# LB-w3-DOUBLE_OR-v03_rev4.net
KiCad netlist of a schematic drawn in EAGLE
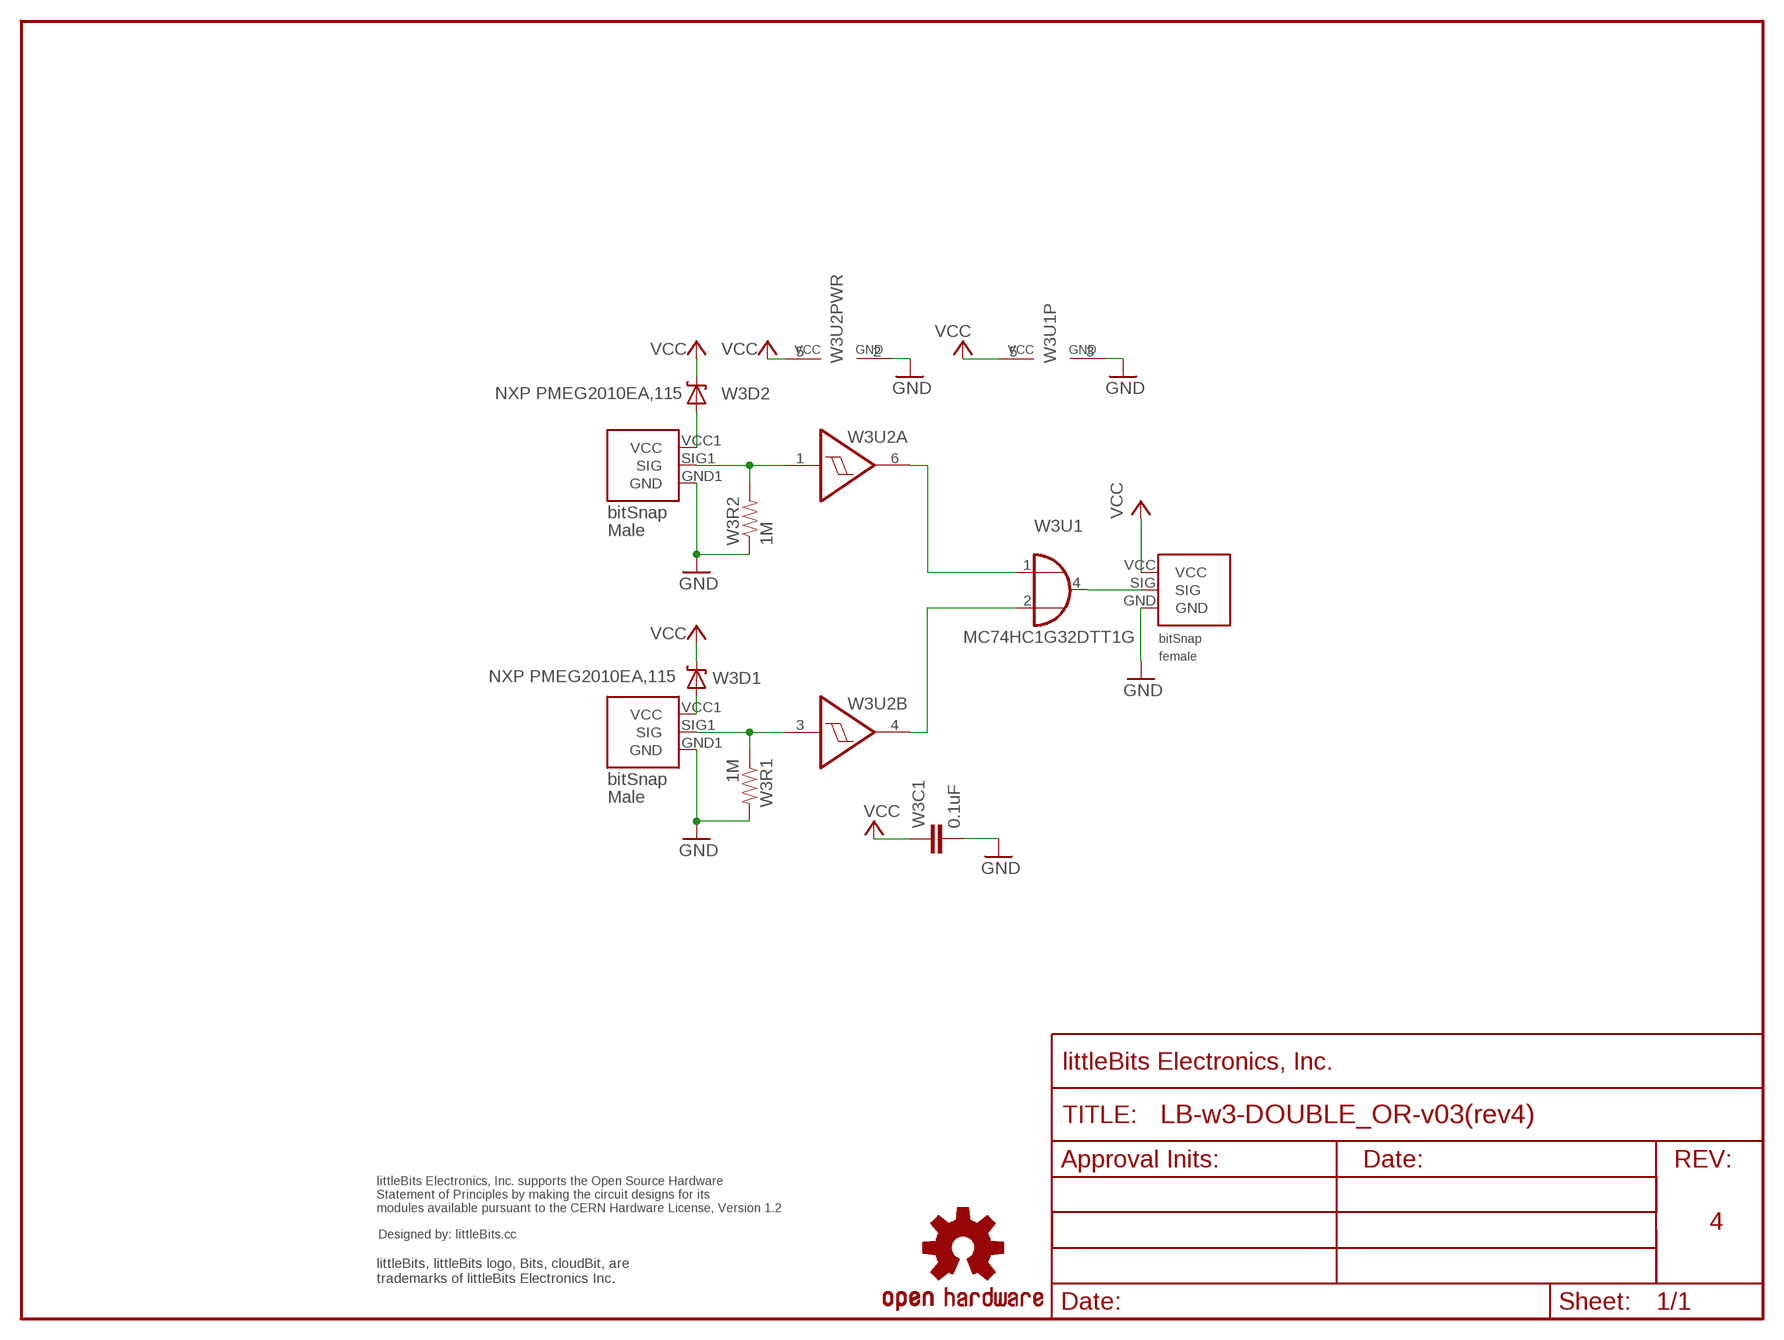
[diagram p0: schematic, sheet 1]

(export (version "E")
  (design (tool "Eeschema 10.0.6"))
  (components
    (comp (ref "U$1")
      (value "OSHWCREDIT")
      (footprint "eagle-import:OSHWCREDIT")
      (libsource (lib "eagle-import") (part "OSHWCREDIT"))
    )
    (comp (ref "U$2")
      (value "OSHW-LOGOL")
      (footprint "eagle-import:OSHW-LOGO-L")
      (libsource (lib "eagle-import") (part "OSHW-LOGOL"))
    )
    (comp (ref "U$16")
      (value "FRAME-LETTER-OHWOHW")
      (footprint "eagle-import:FABDWG01-OHW")
      (libsource (lib "eagle-import") (part "FRAME-LETTER-OHWOHW"))
    )
    (comp (ref "W3BSF1")
      (value "BITSNAP_V03_FEMALE")
      (footprint "eagle-import:BITSNAP_V03_FEMALE")
      (libsource (lib "eagle-import") (part "BITSNAP_V03_FEMALE"))
    )
    (comp (ref "W3BSM1")
      (value "BITSNAP_V03_MALE")
      (footprint "eagle-import:BITSNAP_V03_MALE")
      (libsource (lib "eagle-import") (part "BITSNAP_V03_MALE"))
    )
    (comp (ref "W3BSM2")
      (value "BITSNAP_V03_MALE")
      (footprint "eagle-import:BITSNAP_V03_MALE")
      (libsource (lib "eagle-import") (part "BITSNAP_V03_MALE"))
    )
    (comp (ref "W3C1")
      (value "0.1uF")
      (footprint "eagle-import:CAP-0603")
      (libsource (lib "eagle-import") (part "CAPCAP-0603"))
    )
    (comp (ref "W3D1")
      (value "NXP PMEG2010EA,115")
      (footprint "eagle-import:SOD-323")
      (libsource (lib "eagle-import") (part "DIODE-ZENER-BZT52"))
    )
    (comp (ref "W3D2")
      (value "NXP PMEG2010EA,115")
      (footprint "eagle-import:SOD-323")
      (libsource (lib "eagle-import") (part "DIODE-ZENER-BZT52"))
    )
    (comp (ref "W3R1")
      (value "1M")
      (footprint "eagle-import:0603-RES")
      (libsource (lib "eagle-import") (part "RESISTOR0603-RES"))
    )
    (comp (ref "W3R2")
      (value "1M")
      (footprint "eagle-import:0603-RES")
      (libsource (lib "eagle-import") (part "RESISTOR0603-RES"))
    )
    (comp (ref "W3U1")
      (value "74AUC1G32DBV")
      (footprint "eagle-import:SOT23-5")
      (libsource (lib "eagle-import") (part "741G32DBVAUC"))
    )
    (comp (ref "W3U2")
      (value "SCHMITT_TRIGGER_NON_INVERTING NC7WZ17")
      (footprint "eagle-import:SC70-6")
      (libsource (lib "eagle-import") (part "SCHMITT_TRIGGER_NON_INVERTINGNC7WZ17"))
    )
  )
  (nets
    (net (code "1") (name "GND") (class "Default")
      (node (ref "W3BSF1") (pin "GND") (pinfunction "GND_GND") (pintype "bidirectional"))
      (node (ref "W3BSM1") (pin "GND1") (pinfunction "GND_GND1") (pintype "bidirectional"))
      (node (ref "W3BSM2") (pin "GND1") (pinfunction "GND_GND1") (pintype "bidirectional"))
      (node (ref "W3C1") (pin "2") (pinfunction "2_2") (pintype "passive"))
      (node (ref "W3R1") (pin "2") (pinfunction "2_2") (pintype "passive"))
      (node (ref "W3R2") (pin "1") (pinfunction "1_1") (pintype "passive"))
      (node (ref "W3U1") (pin "3") (pinfunction "GND_3") (pintype "power_in"))
      (node (ref "W3U2") (pin "2") (pinfunction "GND_2") (pintype "power_in"))
    )
    (net (code "2") (name "Net-(W3BSM1-SIG)") (class "Default")
      (node (ref "W3BSM1") (pin "SIG1") (pinfunction "SIG_SIG1") (pintype "bidirectional"))
      (node (ref "W3R2") (pin "2") (pinfunction "2_2") (pintype "passive"))
      (node (ref "W3U2") (pin "1") (pinfunction "I_1") (pintype "input"))
    )
    (net (code "3") (name "Net-(W3BSM1-VCC)") (class "Default")
      (node (ref "W3BSM1") (pin "VCC1") (pinfunction "VCC_VCC1") (pintype "bidirectional"))
      (node (ref "W3D2") (pin "2") (pinfunction "A_2") (pintype "passive"))
    )
    (net (code "4") (name "Net-(W3BSM2-SIG)") (class "Default")
      (node (ref "W3BSM2") (pin "SIG1") (pinfunction "SIG_SIG1") (pintype "bidirectional"))
      (node (ref "W3R1") (pin "1") (pinfunction "1_1") (pintype "passive"))
      (node (ref "W3U2") (pin "3") (pinfunction "I_3") (pintype "input"))
    )
    (net (code "5") (name "Net-(W3BSM2-VCC)") (class "Default")
      (node (ref "W3BSM2") (pin "VCC1") (pinfunction "VCC_VCC1") (pintype "bidirectional"))
      (node (ref "W3D1") (pin "2") (pinfunction "A_2") (pintype "passive"))
    )
    (net (code "6") (name "Net-(W3U1A-I0)") (class "Default")
      (node (ref "W3U1") (pin "1") (pinfunction "I0_1") (pintype "input"))
      (node (ref "W3U2") (pin "6") (pinfunction "O_6") (pintype "output"))
    )
    (net (code "7") (name "Net-(W3U1A-I1)") (class "Default")
      (node (ref "W3U1") (pin "2") (pinfunction "I1_2") (pintype "input"))
      (node (ref "W3U2") (pin "4") (pinfunction "O_4") (pintype "output"))
    )
    (net (code "8") (name "Net-(W3U1A-O)") (class "Default")
      (node (ref "W3BSF1") (pin "SIG") (pinfunction "SIG_SIG") (pintype "bidirectional"))
      (node (ref "W3U1") (pin "4") (pinfunction "O_4") (pintype "output"))
    )
    (net (code "9") (name "VCC") (class "Default")
      (node (ref "W3BSF1") (pin "VCC") (pinfunction "VCC_VCC") (pintype "bidirectional"))
      (node (ref "W3C1") (pin "1") (pinfunction "1_1") (pintype "passive"))
      (node (ref "W3D1") (pin "1") (pinfunction "C_1") (pintype "passive"))
      (node (ref "W3D2") (pin "1") (pinfunction "C_1") (pintype "passive"))
      (node (ref "W3U1") (pin "5") (pinfunction "VCC_5") (pintype "power_in"))
      (node (ref "W3U2") (pin "5") (pinfunction "VCC_5") (pintype "power_in"))
    )
  )
)
